# second_Platine_Power.net
KiCad netlist of a schematic drawn in EAGLE
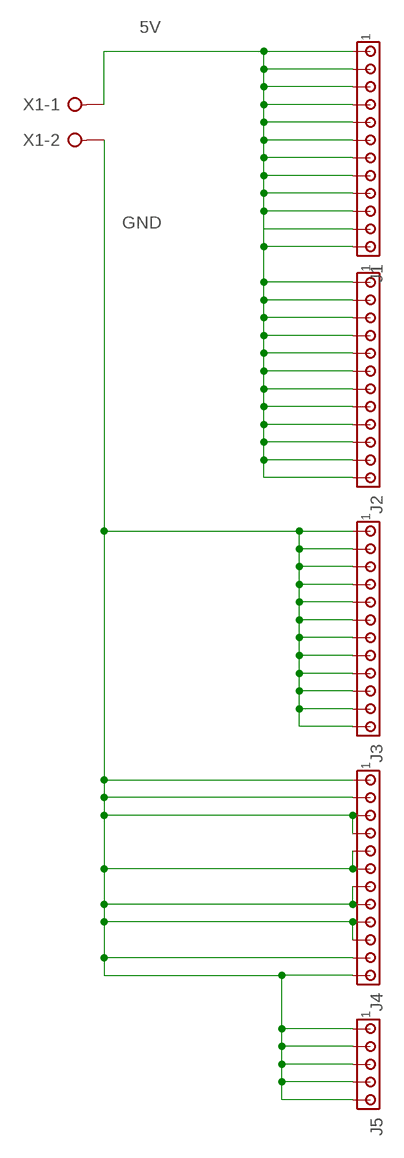
[diagram p0: schematic, sheet 1]

(export (version "E")
  (design (tool "Eeschema 10.0.6"))
  (components
    (comp (ref "J1")
      (value "MTA12-156")
      (footprint "eagle-import:1X12MTA")
      (libsource (lib "eagle-import") (part "MTA12-156"))
    )
    (comp (ref "J2")
      (value "MTA12-156")
      (footprint "eagle-import:1X12MTA")
      (libsource (lib "eagle-import") (part "MTA12-156"))
    )
    (comp (ref "J3")
      (value "MTA12-156")
      (footprint "eagle-import:1X12MTA")
      (libsource (lib "eagle-import") (part "MTA12-156"))
    )
    (comp (ref "J4")
      (value "MTA12-156")
      (footprint "eagle-import:1X12MTA")
      (libsource (lib "eagle-import") (part "MTA12-156"))
    )
    (comp (ref "J5")
      (value "MTA05-156")
      (footprint "eagle-import:1X5MTA")
      (libsource (lib "eagle-import") (part "MTA05-156"))
    )
    (comp (ref "X1")
      (value "W237-02P")
      (footprint "eagle-import:W237-132")
      (libsource (lib "eagle-import") (part "W237-02P"))
    )
  )
  (nets
    (net (code "1") (name "/5V") (class "Default")
      (node (ref "J1") (pin "1") (pinfunction "1_1") (pintype "passive"))
      (node (ref "J1") (pin "10") (pinfunction "10_10") (pintype "passive"))
      (node (ref "J1") (pin "11") (pinfunction "11_11") (pintype "passive"))
      (node (ref "J1") (pin "12") (pinfunction "12_12") (pintype "passive"))
      (node (ref "J1") (pin "2") (pinfunction "2_2") (pintype "passive"))
      (node (ref "J1") (pin "3") (pinfunction "3_3") (pintype "passive"))
      (node (ref "J1") (pin "4") (pinfunction "4_4") (pintype "passive"))
      (node (ref "J1") (pin "5") (pinfunction "5_5") (pintype "passive"))
      (node (ref "J1") (pin "6") (pinfunction "6_6") (pintype "passive"))
      (node (ref "J1") (pin "7") (pinfunction "7_7") (pintype "passive"))
      (node (ref "J1") (pin "8") (pinfunction "8_8") (pintype "passive"))
      (node (ref "J1") (pin "9") (pinfunction "9_9") (pintype "passive"))
      (node (ref "J2") (pin "1") (pinfunction "1_1") (pintype "passive"))
      (node (ref "J2") (pin "10") (pinfunction "10_10") (pintype "passive"))
      (node (ref "J2") (pin "11") (pinfunction "11_11") (pintype "passive"))
      (node (ref "J2") (pin "12") (pinfunction "12_12") (pintype "passive"))
      (node (ref "J2") (pin "2") (pinfunction "2_2") (pintype "passive"))
      (node (ref "J2") (pin "3") (pinfunction "3_3") (pintype "passive"))
      (node (ref "J2") (pin "4") (pinfunction "4_4") (pintype "passive"))
      (node (ref "J2") (pin "5") (pinfunction "5_5") (pintype "passive"))
      (node (ref "J2") (pin "6") (pinfunction "6_6") (pintype "passive"))
      (node (ref "J2") (pin "7") (pinfunction "7_7") (pintype "passive"))
      (node (ref "J2") (pin "8") (pinfunction "8_8") (pintype "passive"))
      (node (ref "J2") (pin "9") (pinfunction "9_9") (pintype "passive"))
      (node (ref "X1") (pin "1") (pinfunction "KL_1") (pintype "passive"))
    )
    (net (code "2") (name "/GND") (class "Default")
      (node (ref "J3") (pin "1") (pinfunction "1_1") (pintype "passive"))
      (node (ref "J3") (pin "10") (pinfunction "10_10") (pintype "passive"))
      (node (ref "J3") (pin "11") (pinfunction "11_11") (pintype "passive"))
      (node (ref "J3") (pin "12") (pinfunction "12_12") (pintype "passive"))
      (node (ref "J3") (pin "2") (pinfunction "2_2") (pintype "passive"))
      (node (ref "J3") (pin "3") (pinfunction "3_3") (pintype "passive"))
      (node (ref "J3") (pin "4") (pinfunction "4_4") (pintype "passive"))
      (node (ref "J3") (pin "5") (pinfunction "5_5") (pintype "passive"))
      (node (ref "J3") (pin "6") (pinfunction "6_6") (pintype "passive"))
      (node (ref "J3") (pin "7") (pinfunction "7_7") (pintype "passive"))
      (node (ref "J3") (pin "8") (pinfunction "8_8") (pintype "passive"))
      (node (ref "J3") (pin "9") (pinfunction "9_9") (pintype "passive"))
      (node (ref "J4") (pin "1") (pinfunction "1_1") (pintype "passive"))
      (node (ref "J4") (pin "10") (pinfunction "10_10") (pintype "passive"))
      (node (ref "J4") (pin "11") (pinfunction "11_11") (pintype "passive"))
      (node (ref "J4") (pin "12") (pinfunction "12_12") (pintype "passive"))
      (node (ref "J4") (pin "2") (pinfunction "2_2") (pintype "passive"))
      (node (ref "J4") (pin "3") (pinfunction "3_3") (pintype "passive"))
      (node (ref "J4") (pin "4") (pinfunction "4_4") (pintype "passive"))
      (node (ref "J4") (pin "5") (pinfunction "5_5") (pintype "passive"))
      (node (ref "J4") (pin "6") (pinfunction "6_6") (pintype "passive"))
      (node (ref "J4") (pin "7") (pinfunction "7_7") (pintype "passive"))
      (node (ref "J4") (pin "8") (pinfunction "8_8") (pintype "passive"))
      (node (ref "J4") (pin "9") (pinfunction "9_9") (pintype "passive"))
      (node (ref "J5") (pin "1") (pinfunction "1_1") (pintype "passive"))
      (node (ref "J5") (pin "2") (pinfunction "2_2") (pintype "passive"))
      (node (ref "J5") (pin "3") (pinfunction "3_3") (pintype "passive"))
      (node (ref "J5") (pin "4") (pinfunction "4_4") (pintype "passive"))
      (node (ref "J5") (pin "5") (pinfunction "5_5") (pintype "passive"))
      (node (ref "X1") (pin "2") (pinfunction "KL_2") (pintype "passive"))
    )
  )
)
